# wendor_motor.net
KiCad netlist of a schematic drawn in EAGLE
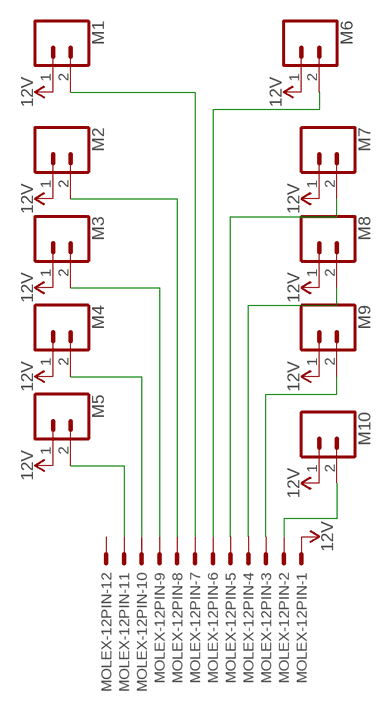
[diagram p0: schematic, sheet 1]

(export (version "E")
  (design (tool "Eeschema 10.0.6"))
  (components
    (comp (ref "M1")
      (value "CONN_02")
      (footprint "eagle-import:1X02")
      (libsource (lib "eagle-import") (part "CONN_02"))
    )
    (comp (ref "M2")
      (value "CONN_02")
      (footprint "eagle-import:1X02")
      (libsource (lib "eagle-import") (part "CONN_02"))
    )
    (comp (ref "M3")
      (value "CONN_02")
      (footprint "eagle-import:1X02")
      (libsource (lib "eagle-import") (part "CONN_02"))
    )
    (comp (ref "M4")
      (value "CONN_02")
      (footprint "eagle-import:1X02")
      (libsource (lib "eagle-import") (part "CONN_02"))
    )
    (comp (ref "M5")
      (value "CONN_02")
      (footprint "eagle-import:1X02")
      (libsource (lib "eagle-import") (part "CONN_02"))
    )
    (comp (ref "M6")
      (value "CONN_02")
      (footprint "eagle-import:1X02")
      (libsource (lib "eagle-import") (part "CONN_02"))
    )
    (comp (ref "M7")
      (value "CONN_02")
      (footprint "eagle-import:1X02")
      (libsource (lib "eagle-import") (part "CONN_02"))
    )
    (comp (ref "M8")
      (value "CONN_02")
      (footprint "eagle-import:1X02")
      (libsource (lib "eagle-import") (part "CONN_02"))
    )
    (comp (ref "M9")
      (value "CONN_02")
      (footprint "eagle-import:1X02")
      (libsource (lib "eagle-import") (part "CONN_02"))
    )
    (comp (ref "M10")
      (value "CONN_02")
      (footprint "eagle-import:1X02")
      (libsource (lib "eagle-import") (part "CONN_02"))
    )
    (comp (ref "MOLEX-12PIN")
      (value "5566-12")
      (footprint "eagle-import:5566-12")
      (fields (field (name "MF") "MOLEX"))
      (libsource (lib "eagle-import") (part "5566-12"))
    )
  )
  (nets
    (net (code "1") (name "12V") (class "Default")
      (node (ref "M1") (pin "1") (pinfunction "1_1") (pintype "passive"))
      (node (ref "M10") (pin "1") (pinfunction "1_1") (pintype "passive"))
      (node (ref "M2") (pin "1") (pinfunction "1_1") (pintype "passive"))
      (node (ref "M3") (pin "1") (pinfunction "1_1") (pintype "passive"))
      (node (ref "M4") (pin "1") (pinfunction "1_1") (pintype "passive"))
      (node (ref "M5") (pin "1") (pinfunction "1_1") (pintype "passive"))
      (node (ref "M6") (pin "1") (pinfunction "1_1") (pintype "passive"))
      (node (ref "M7") (pin "1") (pinfunction "1_1") (pintype "passive"))
      (node (ref "M8") (pin "1") (pinfunction "1_1") (pintype "passive"))
      (node (ref "M9") (pin "1") (pinfunction "1_1") (pintype "passive"))
      (node (ref "MOLEX-12PIN") (pin "1") (pinfunction "S_1") (pintype "passive"))
    )
    (net (code "2") (name "Net-(MOLEX-12PINB-S)") (class "Default")
      (node (ref "M4") (pin "2") (pinfunction "2_2") (pintype "passive"))
      (node (ref "MOLEX-12PIN") (pin "10") (pinfunction "S_10") (pintype "passive"))
    )
    (net (code "3") (name "Net-(MOLEX-12PINC-S)") (class "Default")
      (node (ref "M5") (pin "2") (pinfunction "2_2") (pintype "passive"))
      (node (ref "MOLEX-12PIN") (pin "11") (pinfunction "S_11") (pintype "passive"))
    )
    (net (code "4") (name "Net-(MOLEX-12PINE-S)") (class "Default")
      (node (ref "M10") (pin "2") (pinfunction "2_2") (pintype "passive"))
      (node (ref "MOLEX-12PIN") (pin "2") (pinfunction "S_2") (pintype "passive"))
    )
    (net (code "5") (name "Net-(MOLEX-12PINF-S)") (class "Default")
      (node (ref "M9") (pin "2") (pinfunction "2_2") (pintype "passive"))
      (node (ref "MOLEX-12PIN") (pin "3") (pinfunction "S_3") (pintype "passive"))
    )
    (net (code "6") (name "Net-(MOLEX-12PING-S)") (class "Default")
      (node (ref "M8") (pin "2") (pinfunction "2_2") (pintype "passive"))
      (node (ref "MOLEX-12PIN") (pin "4") (pinfunction "S_4") (pintype "passive"))
    )
    (net (code "7") (name "Net-(MOLEX-12PINH-S)") (class "Default")
      (node (ref "M7") (pin "2") (pinfunction "2_2") (pintype "passive"))
      (node (ref "MOLEX-12PIN") (pin "5") (pinfunction "S_5") (pintype "passive"))
    )
    (net (code "8") (name "Net-(MOLEX-12PINI-S)") (class "Default")
      (node (ref "M6") (pin "2") (pinfunction "2_2") (pintype "passive"))
      (node (ref "MOLEX-12PIN") (pin "6") (pinfunction "S_6") (pintype "passive"))
    )
    (net (code "9") (name "Net-(MOLEX-12PINJ-S)") (class "Default")
      (node (ref "M1") (pin "2") (pinfunction "2_2") (pintype "passive"))
      (node (ref "MOLEX-12PIN") (pin "7") (pinfunction "S_7") (pintype "passive"))
    )
    (net (code "10") (name "Net-(MOLEX-12PINK-S)") (class "Default")
      (node (ref "M2") (pin "2") (pinfunction "2_2") (pintype "passive"))
      (node (ref "MOLEX-12PIN") (pin "8") (pinfunction "S_8") (pintype "passive"))
    )
    (net (code "11") (name "Net-(MOLEX-12PINL-S)") (class "Default")
      (node (ref "M3") (pin "2") (pinfunction "2_2") (pintype "passive"))
      (node (ref "MOLEX-12PIN") (pin "9") (pinfunction "S_9") (pintype "passive"))
    )
    (net (code "12") (name "unconnected-(MOLEX-12PIND-S-Pad12)") (class "Default")
      (node (ref "MOLEX-12PIN") (pin "12") (pinfunction "S_12") (pintype "passive"))
    )
  )
)
